# FPGA_ADC2.net
KiCad netlist of a schematic drawn in Altium Designer
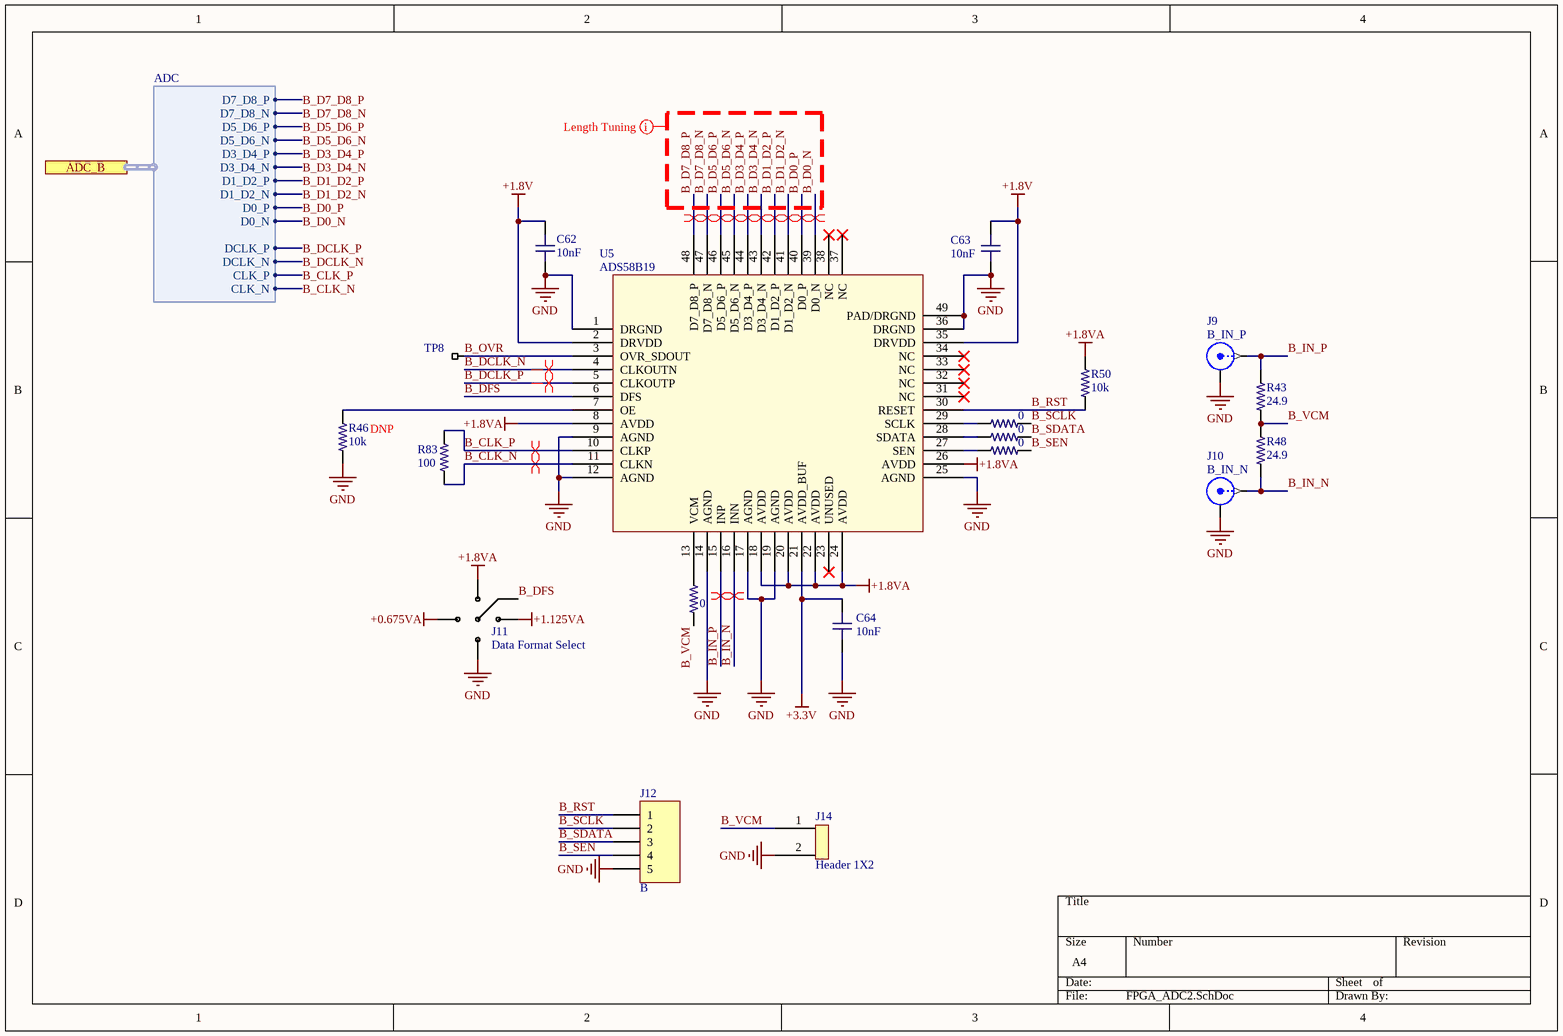
[diagram p0: FPGA_ADC2.SchDoc]

(export (version "E")
  (design (tool "Eeschema 10.0.6"))
  (components
    (comp (ref "C62")
      (value "10nF")
      (footprint "C0603-HIGH-DENSITY")
      (description "CAP CER 10000PF 50V X7R 0603")
      (fields (field (name "Comment") "C0603 10nF 50V X7R"))
      (libsource (lib "Capacitors") (part "C0603 10nF 50V X7R"))
    )
    (comp (ref "C63")
      (value "10nF")
      (footprint "C0603-HIGH-DENSITY")
      (description "CAP CER 10000PF 50V X7R 0603")
      (fields (field (name "Comment") "C0603 10nF 50V X7R"))
      (libsource (lib "Capacitors") (part "C0603 10nF 50V X7R"))
    )
    (comp (ref "C64")
      (value "10nF")
      (footprint "C0603-HIGH-DENSITY")
      (description "CAP CER 10000PF 50V X7R 0603")
      (fields (field (name "Comment") "C0603 10nF 50V X7R"))
      (libsource (lib "Capacitors") (part "C0603 10nF 50V X7R"))
    )
    (comp (ref "J9")
      (value "B_IN_P")
      (footprint "SMA Edge Launch (Horizontal)")
      (description "SMA Connector")
      (libsource (lib "Connectors") (part "SMA"))
    )
    (comp (ref "J10")
      (value "B_IN_N")
      (footprint "SMA Edge Launch (Horizontal)")
      (description "SMA Connector")
      (libsource (lib "Connectors") (part "SMA"))
    )
    (comp (ref "J11")
      (value "Data Format Select")
      (footprint "4P Jumper")
      (description "0603 4 Way Solder Jumper")
      (libsource (lib "Switches") (part "4P Jumper"))
    )
    (comp (ref "J12")
      (value "B")
      (footprint "HDR1X5")
      (description "Header, 5-Pin")
      (fields (field (name "PUBLISHER") "Altium Limited"))
      (libsource (lib "Miscellaneous Connectors") (part "Header 5"))
    )
    (comp (ref "J14")
      (value "Header 1X2")
      (footprint "Header 1x2 TH Pitch 2.54mm")
      (libsource (lib "Connectors") (part "Header 1X2"))
    )
    (comp (ref "R43")
      (value "24.9")
      (footprint "R0603-HIGH-DENSITY")
      (description "Chip Resistor, 0603, 24.9 ohms, 0.1W")
      (fields (field (name "Comment") "RC0603FR-0724R9L"))
      (libsource (lib "Resistors") (part "R0603 24.9R 1%"))
    )
    (comp (ref "R44")
      (value "0")
      (footprint "R0603-IPC")
      (description "RES SMD 0 OHM JUMPER 1/10W 0603")
      (fields (field (name "Comment") "R0603 0"))
      (libsource (lib "Resistors") (part "R0603 0"))
    )
    (comp (ref "R45")
      (value "0")
      (footprint "R0603-IPC")
      (description "RES SMD 0 OHM JUMPER 1/10W 0603")
      (fields (field (name "Comment") "R0603 0"))
      (libsource (lib "Resistors") (part "R0603 0"))
    )
    (comp (ref "R46")
      (value "10k")
      (footprint "R0603-IPC-10K")
      (description "RES SMD 10K OHM 1% 1/10W 0603")
      (fields (field (name "Comment") "R0603 10K 1%"))
      (libsource (lib "Resistors") (part "R0603 10K 1%"))
    )
    (comp (ref "R47")
      (value "0")
      (footprint "R0603-IPC")
      (description "RES SMD 0 OHM JUMPER 1/10W 0603")
      (fields (field (name "Comment") "R0603 0"))
      (libsource (lib "Resistors") (part "R0603 0"))
    )
    (comp (ref "R48")
      (value "24.9")
      (footprint "R0603-HIGH-DENSITY")
      (description "Chip Resistor, 0603, 24.9 ohms, 0.1W")
      (fields (field (name "Comment") "RC0603FR-0724R9L"))
      (libsource (lib "Resistors") (part "R0603 24.9R 1%"))
    )
    (comp (ref "R49")
      (value "0")
      (footprint "R0603-IPC")
      (description "RES SMD 0 OHM JUMPER 1/10W 0603")
      (fields (field (name "Comment") "R0603 0"))
      (libsource (lib "Resistors") (part "R0603 0"))
    )
    (comp (ref "R50")
      (value "10k")
      (footprint "R0603-IPC-10K")
      (description "RES SMD 10K OHM 1% 1/10W 0603")
      (fields (field (name "Comment") "R0603 10K 1%"))
      (libsource (lib "Resistors") (part "R0603 10K 1%"))
    )
    (comp (ref "R83")
      (value "100")
      (footprint "R0402-HIGH-DENSITY")
      (description "Chip Resistor, 0402, 100 ohms, 1%, 1/16 W")
      (fields (field (name "Comment") "R0402 100R 1%"))
      (libsource (lib "Resistors") (part "R0402 100R 1%"))
    )
    (comp (ref "TP8")
      (value "Testpoint_SMT")
      (footprint "TESTPOINT_SMT")
      (description "SMT Test Point")
      (libsource (lib "Virtual Parts") (part "Testpoint_SMT"))
    )
    (comp (ref "U5")
      (value "ADS58B19")
      (footprint "VQFN48")
      (description "Single ADC Pipelined 250Msps 9-bit Parallel/LVDS 48-Pin VQFN")
      (libsource (lib "Integrated Circuits") (part "ADS58B19"))
    )
  )
  (nets
    (net (code "2") (name "+0.675VA") (class "Default")
      (node (ref "J11") (pin "4") (pinfunction "4_4") (pintype "passive"))
    )
    (net (code "3") (name "+1.8V") (class "Default")
      (node (ref "C62") (pin "1") (pintype "passive"))
      (node (ref "C63") (pin "1") (pintype "passive"))
      (node (ref "U5") (pin "2") (pinfunction "DRVDD_2") (pintype "passive"))
      (node (ref "U5") (pin "35") (pinfunction "DRVDD_35") (pintype "passive"))
    )
    (net (code "4") (name "+1.8VA") (class "Default")
      (node (ref "J11") (pin "1") (pinfunction "1_1") (pintype "passive"))
      (node (ref "R50") (pin "2") (pintype "passive"))
      (node (ref "U5") (pin "18") (pinfunction "AVDD_18") (pintype "passive"))
      (node (ref "U5") (pin "20") (pinfunction "AVDD_20") (pintype "passive"))
      (node (ref "U5") (pin "22") (pinfunction "AVDD_22") (pintype "passive"))
      (node (ref "U5") (pin "24") (pinfunction "AVDD_24") (pintype "passive"))
      (node (ref "U5") (pin "26") (pinfunction "AVDD_26") (pintype "passive"))
      (node (ref "U5") (pin "8") (pinfunction "AVDD_8") (pintype "passive"))
    )
    (net (code "5") (name "+1.125VA") (class "Default")
      (node (ref "J11") (pin "2") (pinfunction "2_2") (pintype "passive"))
    )
    (net (code "6") (name "+3.3V") (class "Default")
      (node (ref "C64") (pin "1") (pintype "passive"))
      (node (ref "U5") (pin "21") (pinfunction "AVDD_BUF_21") (pintype "passive"))
    )
    (net (code "7") (name "/B_CLK_N") (class "Default")
      (node (ref "R83") (pin "1") (pintype "passive"))
      (node (ref "U5") (pin "11") (pinfunction "CLKN_11") (pintype "passive"))
    )
    (net (code "8") (name "/B_CLK_P") (class "Default")
      (node (ref "R83") (pin "2") (pintype "passive"))
      (node (ref "U5") (pin "10") (pinfunction "CLKP_10") (pintype "passive"))
    )
    (net (code "9") (name "/B_D0_N") (class "Default")
      (node (ref "U5") (pin "39") (pinfunction "D0_N_39") (pintype "passive"))
    )
    (net (code "10") (name "/B_D0_P") (class "Default")
      (node (ref "U5") (pin "40") (pinfunction "D0_P_40") (pintype "passive"))
    )
    (net (code "11") (name "/B_D1_D2_N") (class "Default")
      (node (ref "U5") (pin "41") (pinfunction "D1_D2_N_41") (pintype "passive"))
    )
    (net (code "12") (name "/B_D1_D2_P") (class "Default")
      (node (ref "U5") (pin "42") (pinfunction "D1_D2_P_42") (pintype "passive"))
    )
    (net (code "13") (name "/B_D3_D4_N") (class "Default")
      (node (ref "U5") (pin "43") (pinfunction "D3_D4_N_43") (pintype "passive"))
    )
    (net (code "14") (name "/B_D3_D4_P") (class "Default")
      (node (ref "U5") (pin "44") (pinfunction "D3_D4_P_44") (pintype "passive"))
    )
    (net (code "15") (name "/B_D5_D6_N") (class "Default")
      (node (ref "U5") (pin "45") (pinfunction "D5_D6_N_45") (pintype "passive"))
    )
    (net (code "16") (name "/B_D5_D6_P") (class "Default")
      (node (ref "U5") (pin "46") (pinfunction "D5_D6_P_46") (pintype "passive"))
    )
    (net (code "17") (name "/B_D7_D8_N") (class "Default")
      (node (ref "U5") (pin "47") (pinfunction "D7_D8_N_47") (pintype "passive"))
    )
    (net (code "18") (name "/B_D7_D8_P") (class "Default")
      (node (ref "U5") (pin "48") (pinfunction "D7_D8_P_48") (pintype "passive"))
    )
    (net (code "19") (name "/B_DCLK_N") (class "Default")
      (node (ref "U5") (pin "4") (pinfunction "CLKOUTN_4") (pintype "passive"))
    )
    (net (code "20") (name "/B_DCLK_P") (class "Default")
      (node (ref "U5") (pin "5") (pinfunction "CLKOUTP_5") (pintype "passive"))
    )
    (net (code "21") (name "/B_DFS") (class "Default")
      (node (ref "J11") (pin "5") (pinfunction "5_5") (pintype "passive"))
      (node (ref "U5") (pin "6") (pinfunction "DFS_6") (pintype "passive"))
    )
    (net (code "22") (name "/B_IN_N") (class "Default")
      (node (ref "J10") (pin "1") (pinfunction "X_1") (pintype "output"))
      (node (ref "R48") (pin "1") (pintype "passive"))
      (node (ref "U5") (pin "16") (pinfunction "INN_16") (pintype "passive"))
    )
    (net (code "23") (name "/B_IN_P") (class "Default")
      (node (ref "J9") (pin "1") (pinfunction "X_1") (pintype "output"))
      (node (ref "R43") (pin "2") (pintype "passive"))
      (node (ref "U5") (pin "15") (pinfunction "INP_15") (pintype "passive"))
    )
    (net (code "24") (name "/B_OVR") (class "Default")
      (node (ref "TP8") (pin "1") (pinfunction "1_1") (pintype "passive"))
      (node (ref "U5") (pin "3") (pinfunction "OVR_SDOUT_3") (pintype "passive"))
    )
    (net (code "25") (name "/B_RST") (class "Default")
      (node (ref "J12") (pin "1") (pinfunction "1_1") (pintype "passive"))
      (node (ref "R50") (pin "1") (pintype "passive"))
      (node (ref "U5") (pin "30") (pinfunction "RESET_30") (pintype "passive"))
    )
    (net (code "26") (name "/B_SCLK") (class "Default")
      (node (ref "J12") (pin "2") (pinfunction "2_2") (pintype "passive"))
      (node (ref "R44") (pin "2") (pintype "passive"))
    )
    (net (code "27") (name "/B_SDATA") (class "Default")
      (node (ref "J12") (pin "3") (pinfunction "3_3") (pintype "passive"))
      (node (ref "R45") (pin "2") (pintype "passive"))
    )
    (net (code "28") (name "/B_SEN") (class "Default")
      (node (ref "J12") (pin "4") (pinfunction "4_4") (pintype "passive"))
      (node (ref "R47") (pin "2") (pintype "passive"))
    )
    (net (code "29") (name "/B_VCM") (class "Default")
      (node (ref "J14") (pin "1") (pintype "passive"))
      (node (ref "R43") (pin "1") (pintype "passive"))
      (node (ref "R48") (pin "2") (pintype "passive"))
      (node (ref "R49") (pin "2") (pintype "passive"))
    )
    (net (code "31") (name "GND") (class "Default")
      (node (ref "C62") (pin "2") (pintype "passive"))
      (node (ref "C63") (pin "2") (pintype "passive"))
      (node (ref "C64") (pin "2") (pintype "passive"))
      (node (ref "J10") (pin "2") (pinfunction "Y_2") (pintype "power_in"))
      (node (ref "J11") (pin "3") (pinfunction "3_3") (pintype "passive"))
      (node (ref "J12") (pin "5") (pinfunction "5_5") (pintype "passive"))
      (node (ref "J14") (pin "2") (pintype "passive"))
      (node (ref "J9") (pin "2") (pinfunction "Y_2") (pintype "power_in"))
      (node (ref "R46") (pin "1") (pintype "passive"))
      (node (ref "U5") (pin "1") (pinfunction "DRGND_1") (pintype "passive"))
      (node (ref "U5") (pin "12") (pinfunction "AGND_12") (pintype "passive"))
      (node (ref "U5") (pin "14") (pinfunction "AGND_14") (pintype "passive"))
      (node (ref "U5") (pin "17") (pinfunction "AGND_17") (pintype "passive"))
      (node (ref "U5") (pin "19") (pinfunction "AGND_19") (pintype "passive"))
      (node (ref "U5") (pin "25") (pinfunction "AGND_25") (pintype "passive"))
      (node (ref "U5") (pin "36") (pinfunction "DRGND_36") (pintype "passive"))
      (node (ref "U5") (pin "49") (pinfunction "PAD/DRGND_49") (pintype "passive"))
      (node (ref "U5") (pin "9") (pinfunction "AGND_9") (pintype "passive"))
    )
    (net (code "32") (name "Net-(U5-OE)") (class "Default")
      (node (ref "R46") (pin "2") (pintype "passive"))
      (node (ref "U5") (pin "7") (pinfunction "OE_7") (pintype "passive"))
    )
    (net (code "33") (name "Net-(U5-SCLK)") (class "Default")
      (node (ref "R44") (pin "1") (pintype "passive"))
      (node (ref "U5") (pin "29") (pinfunction "SCLK_29") (pintype "passive"))
    )
    (net (code "34") (name "Net-(U5-SDATA)") (class "Default")
      (node (ref "R45") (pin "1") (pintype "passive"))
      (node (ref "U5") (pin "28") (pinfunction "SDATA_28") (pintype "passive"))
    )
    (net (code "35") (name "Net-(U5-SEN)") (class "Default")
      (node (ref "R47") (pin "1") (pintype "passive"))
      (node (ref "U5") (pin "27") (pinfunction "SEN_27") (pintype "passive"))
    )
    (net (code "36") (name "Net-(U5-VCM)") (class "Default")
      (node (ref "R49") (pin "1") (pintype "passive"))
      (node (ref "U5") (pin "13") (pinfunction "VCM_13") (pintype "passive"))
    )
    (net (code "37") (name "unconnected-(U5-NC-Pad31)") (class "Default")
      (node (ref "U5") (pin "31") (pinfunction "NC_31") (pintype "passive+no_connect"))
    )
    (net (code "38") (name "unconnected-(U5-NC-Pad32)") (class "Default")
      (node (ref "U5") (pin "32") (pinfunction "NC_32") (pintype "passive+no_connect"))
    )
    (net (code "39") (name "unconnected-(U5-NC-Pad33)") (class "Default")
      (node (ref "U5") (pin "33") (pinfunction "NC_33") (pintype "passive+no_connect"))
    )
    (net (code "40") (name "unconnected-(U5-NC-Pad34)") (class "Default")
      (node (ref "U5") (pin "34") (pinfunction "NC_34") (pintype "passive+no_connect"))
    )
    (net (code "41") (name "unconnected-(U5-NC-Pad37)") (class "Default")
      (node (ref "U5") (pin "37") (pinfunction "NC_37") (pintype "passive+no_connect"))
    )
    (net (code "42") (name "unconnected-(U5-NC-Pad38)") (class "Default")
      (node (ref "U5") (pin "38") (pinfunction "NC_38") (pintype "passive+no_connect"))
    )
    (net (code "43") (name "unconnected-(U5-UNUSED-Pad23)") (class "Default")
      (node (ref "U5") (pin "23") (pinfunction "UNUSED_23") (pintype "passive+no_connect"))
    )
  )
)
